# d2101-lofi-delay.net
KiCad netlist of a schematic drawn in EAGLE
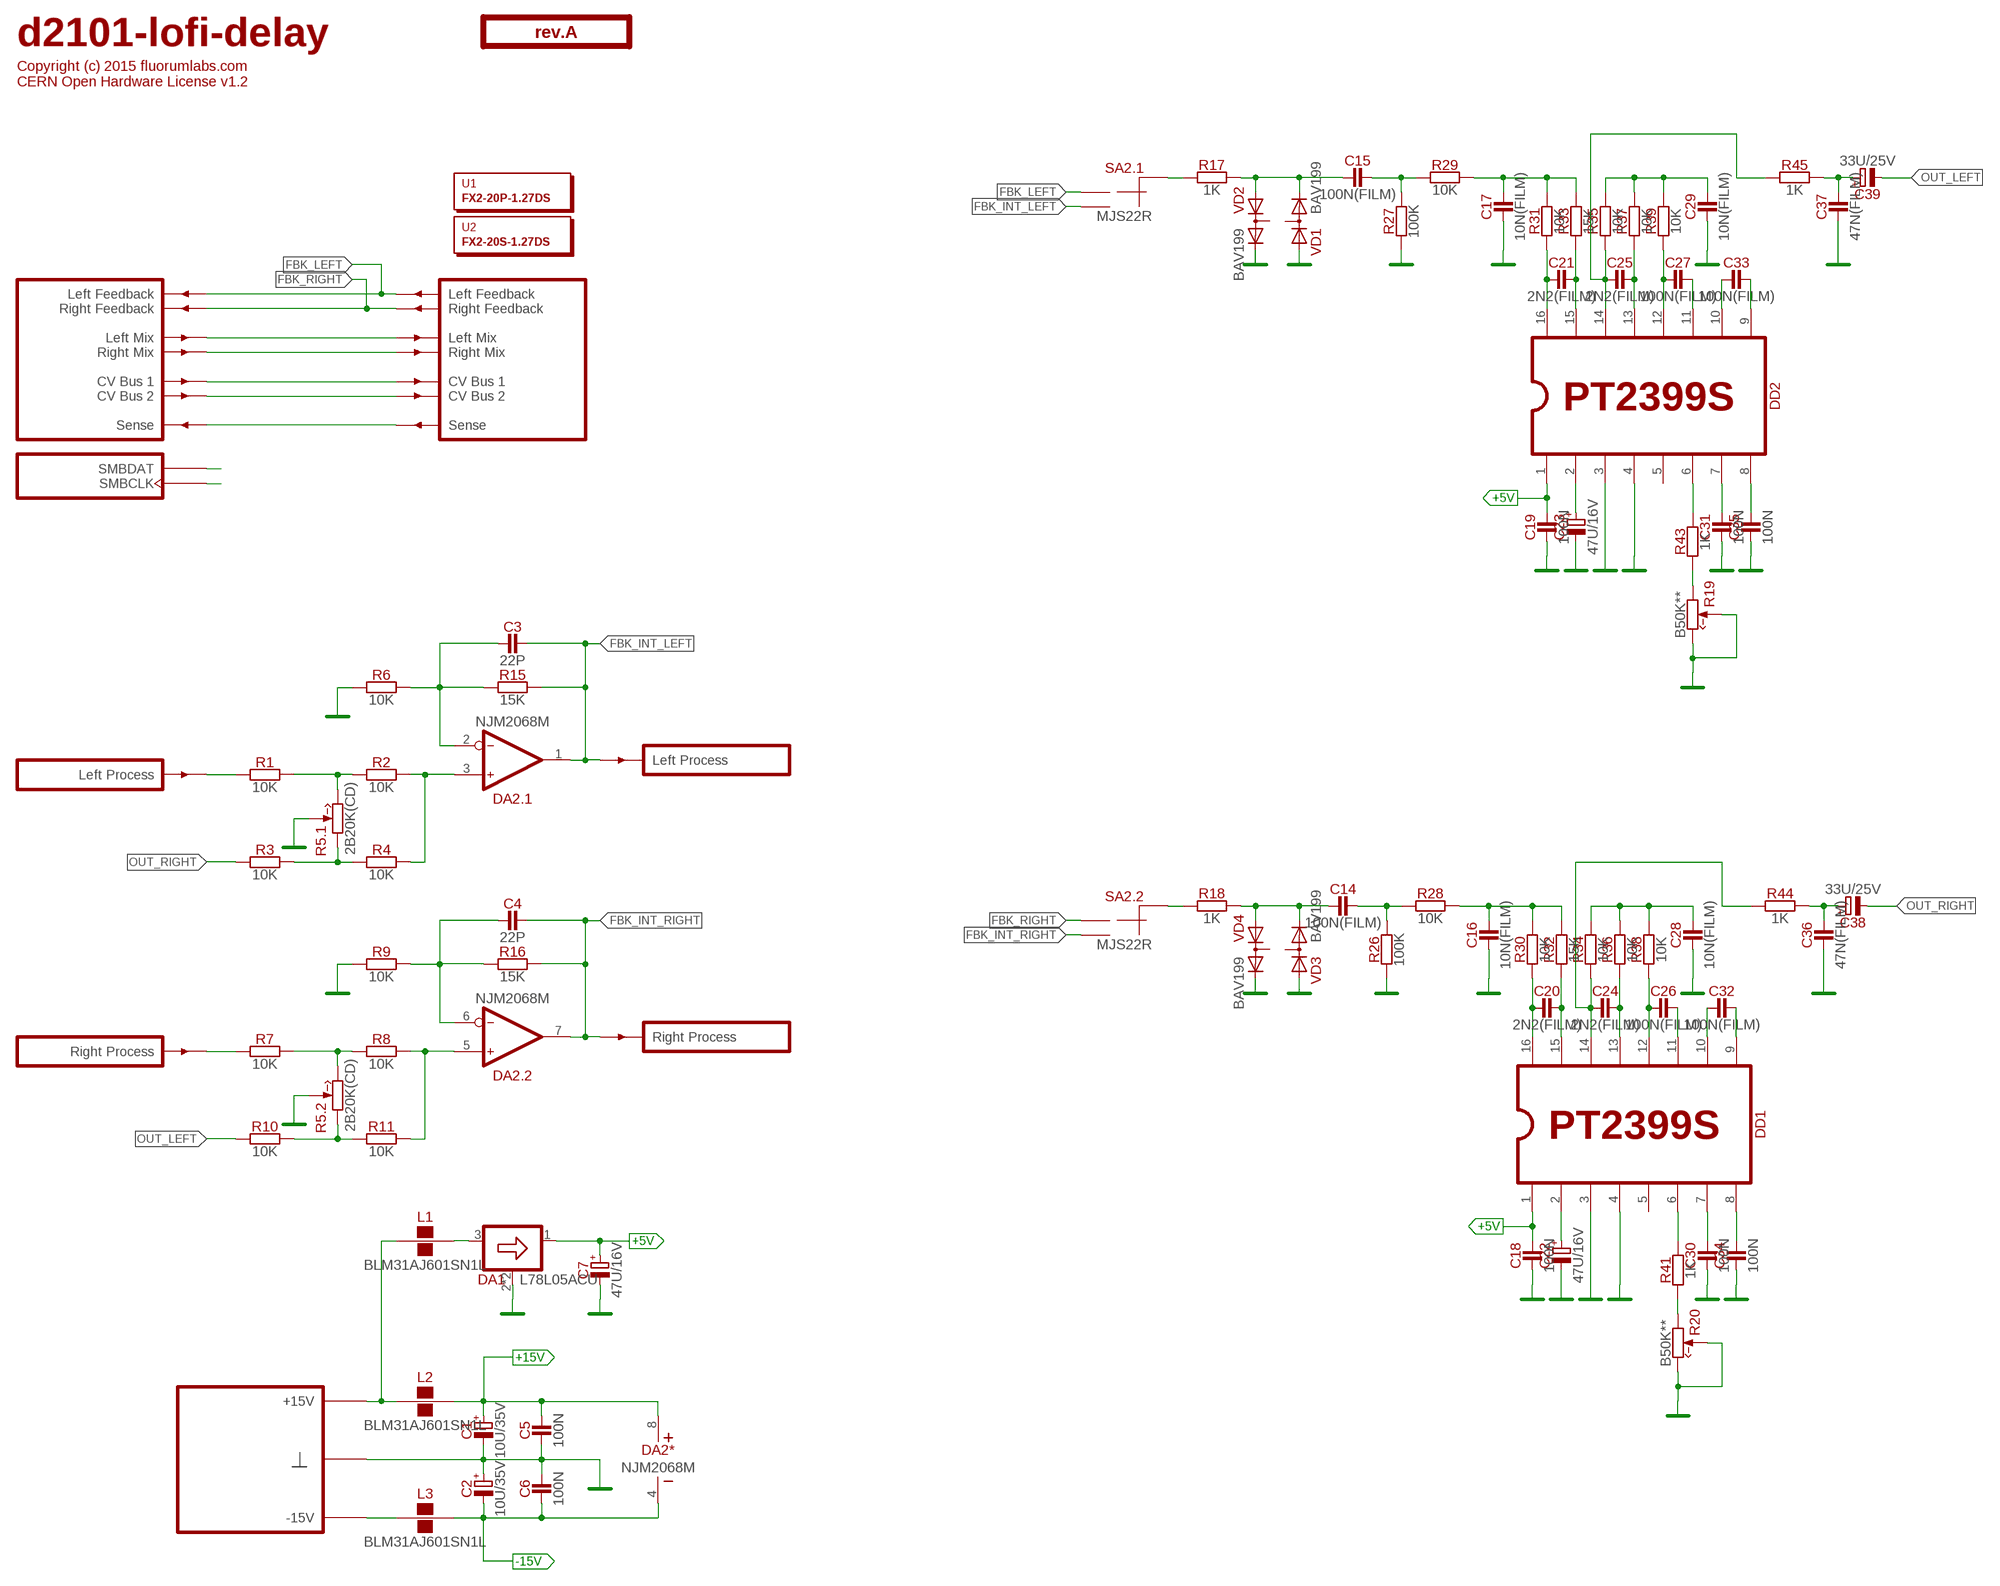
[diagram p0: schematic, sheet 1]

(export (version "E")
  (design (tool "Eeschema 10.0.6"))
  (components
    (comp (ref "C1")
      (value "10U/35V")
      (footprint "eagle-import:E2-5")
      (libsource (lib "eagle-import") (part "?10U/35V"))
    )
    (comp (ref "C2")
      (value "10U/35V")
      (footprint "eagle-import:E2-5")
      (libsource (lib "eagle-import") (part "?10U/35V"))
    )
    (comp (ref "C3")
      (value "22P")
      (footprint "eagle-import:C-0805")
      (libsource (lib "eagle-import") (part "?22P"))
    )
    (comp (ref "C4")
      (value "22P")
      (footprint "eagle-import:C-0805")
      (libsource (lib "eagle-import") (part "?22P"))
    )
    (comp (ref "C5")
      (value "100N")
      (footprint "eagle-import:C-0805")
      (libsource (lib "eagle-import") (part "?100N"))
    )
    (comp (ref "C6")
      (value "100N")
      (footprint "eagle-import:C-0805")
      (libsource (lib "eagle-import") (part "?100N"))
    )
    (comp (ref "C7")
      (value "47U/16V")
      (footprint "eagle-import:E2-5")
      (libsource (lib "eagle-import") (part "?47U/16V"))
    )
    (comp (ref "C14")
      (value "100N(FILM)")
      (footprint "eagle-import:C050-025X075")
      (libsource (lib "eagle-import") (part "?100N(FILM)"))
    )
    (comp (ref "C15")
      (value "100N(FILM)")
      (footprint "eagle-import:C050-025X075")
      (libsource (lib "eagle-import") (part "?100N(FILM)"))
    )
    (comp (ref "C16")
      (value "10N(FILM)")
      (footprint "eagle-import:C050-025X075")
      (libsource (lib "eagle-import") (part "?10N(FILM)"))
    )
    (comp (ref "C17")
      (value "10N(FILM)")
      (footprint "eagle-import:C050-025X075")
      (libsource (lib "eagle-import") (part "?10N(FILM)"))
    )
    (comp (ref "C18")
      (value "100N")
      (footprint "eagle-import:C-0805")
      (libsource (lib "eagle-import") (part "?100N"))
    )
    (comp (ref "C19")
      (value "100N")
      (footprint "eagle-import:C-0805")
      (libsource (lib "eagle-import") (part "?100N"))
    )
    (comp (ref "C20")
      (value "2N2(FILM)")
      (footprint "eagle-import:C050-025X075")
      (libsource (lib "eagle-import") (part "?2N2(FILM)"))
    )
    (comp (ref "C21")
      (value "2N2(FILM)")
      (footprint "eagle-import:C050-025X075")
      (libsource (lib "eagle-import") (part "?2N2(FILM)"))
    )
    (comp (ref "C22")
      (value "47U/16V")
      (footprint "eagle-import:E2-5")
      (libsource (lib "eagle-import") (part "?47U/16V"))
    )
    (comp (ref "C23")
      (value "47U/16V")
      (footprint "eagle-import:E2-5")
      (libsource (lib "eagle-import") (part "?47U/16V"))
    )
    (comp (ref "C24")
      (value "2N2(FILM)")
      (footprint "eagle-import:C050-025X075")
      (libsource (lib "eagle-import") (part "?2N2(FILM)"))
    )
    (comp (ref "C25")
      (value "2N2(FILM)")
      (footprint "eagle-import:C050-025X075")
      (libsource (lib "eagle-import") (part "?2N2(FILM)"))
    )
    (comp (ref "C26")
      (value "100N(FILM)")
      (footprint "eagle-import:C050-025X075")
      (libsource (lib "eagle-import") (part "?100N(FILM)"))
    )
    (comp (ref "C27")
      (value "100N(FILM)")
      (footprint "eagle-import:C050-025X075")
      (libsource (lib "eagle-import") (part "?100N(FILM)"))
    )
    (comp (ref "C28")
      (value "10N(FILM)")
      (footprint "eagle-import:C050-025X075")
      (libsource (lib "eagle-import") (part "?10N(FILM)"))
    )
    (comp (ref "C29")
      (value "10N(FILM)")
      (footprint "eagle-import:C050-025X075")
      (libsource (lib "eagle-import") (part "?10N(FILM)"))
    )
    (comp (ref "C30")
      (value "100N")
      (footprint "eagle-import:C-0805")
      (libsource (lib "eagle-import") (part "?100N"))
    )
    (comp (ref "C31")
      (value "100N")
      (footprint "eagle-import:C-0805")
      (libsource (lib "eagle-import") (part "?100N"))
    )
    (comp (ref "C32")
      (value "100N(FILM)")
      (footprint "eagle-import:C050-025X075")
      (libsource (lib "eagle-import") (part "?100N(FILM)"))
    )
    (comp (ref "C33")
      (value "100N(FILM)")
      (footprint "eagle-import:C050-025X075")
      (libsource (lib "eagle-import") (part "?100N(FILM)"))
    )
    (comp (ref "C34")
      (value "100N")
      (footprint "eagle-import:C-0805")
      (libsource (lib "eagle-import") (part "?100N"))
    )
    (comp (ref "C35")
      (value "100N")
      (footprint "eagle-import:C-0805")
      (libsource (lib "eagle-import") (part "?100N"))
    )
    (comp (ref "C36")
      (value "47N(FILM)")
      (footprint "eagle-import:C050-025X075")
      (libsource (lib "eagle-import") (part "?47N(FILM)"))
    )
    (comp (ref "C37")
      (value "47N(FILM)")
      (footprint "eagle-import:C050-025X075")
      (libsource (lib "eagle-import") (part "?47N(FILM)"))
    )
    (comp (ref "C38")
      (value "33U/25V")
      (footprint "eagle-import:E2,5-7")
      (libsource (lib "eagle-import") (part "?33U/25V"))
    )
    (comp (ref "C39")
      (value "33U/25V")
      (footprint "eagle-import:E2,5-7")
      (libsource (lib "eagle-import") (part "?33U/25V"))
    )
    (comp (ref "DA1")
      (value "L78L05ACU")
      (footprint "eagle-import:SOT89")
      (libsource (lib "eagle-import") (part "?L78L05ACU"))
    )
    (comp (ref "DA2")
      (value "NJM2068M")
      (footprint "eagle-import:SO-8")
      (libsource (lib "eagle-import") (part "NJM2068M"))
    )
    (comp (ref "DD1")
      (value "PT2399S")
      (footprint "eagle-import:SO-16")
      (libsource (lib "eagle-import") (part "PT2399S"))
    )
    (comp (ref "DD2")
      (value "PT2399S")
      (footprint "eagle-import:SO-16")
      (libsource (lib "eagle-import") (part "PT2399S"))
    )
    (comp (ref "L1")
      (value "BLM31AJ601SN1L")
      (footprint "eagle-import:1206")
      (libsource (lib "eagle-import") (part "BLM31AJ601SN1L"))
    )
    (comp (ref "L2")
      (value "BLM31AJ601SN1L")
      (footprint "eagle-import:1206")
      (libsource (lib "eagle-import") (part "BLM31AJ601SN1L"))
    )
    (comp (ref "L3")
      (value "BLM31AJ601SN1L")
      (footprint "eagle-import:1206")
      (libsource (lib "eagle-import") (part "BLM31AJ601SN1L"))
    )
    (comp (ref "O1")
      (value "TITLE")
      (footprint "eagle-import:EMPTY")
      (libsource (lib "eagle-import") (part "TITLE"))
    )
    (comp (ref "PCB1")
      (value "rev.A")
      (footprint "eagle-import:ST2-BOARD-50")
      (libsource (lib "eagle-import") (part "ST2-BOARD-50"))
    )
    (comp (ref "R1")
      (value "10K")
      (footprint "eagle-import:R-0805")
      (libsource (lib "eagle-import") (part "?10K"))
    )
    (comp (ref "R2")
      (value "10K")
      (footprint "eagle-import:R-0805")
      (libsource (lib "eagle-import") (part "?10K"))
    )
    (comp (ref "R3")
      (value "10K")
      (footprint "eagle-import:R-0805")
      (libsource (lib "eagle-import") (part "?10K"))
    )
    (comp (ref "R4")
      (value "10K")
      (footprint "eagle-import:R-0805")
      (libsource (lib "eagle-import") (part "?10K"))
    )
    (comp (ref "R5")
      (value "2B20K(CD)")
      (footprint "eagle-import:RV11-DUAL")
      (libsource (lib "eagle-import") (part "2?B20K(CD)"))
    )
    (comp (ref "R6")
      (value "10K")
      (footprint "eagle-import:R-0805")
      (libsource (lib "eagle-import") (part "?10K"))
    )
    (comp (ref "R7")
      (value "10K")
      (footprint "eagle-import:R-0805")
      (libsource (lib "eagle-import") (part "?10K"))
    )
    (comp (ref "R8")
      (value "10K")
      (footprint "eagle-import:R-0805")
      (libsource (lib "eagle-import") (part "?10K"))
    )
    (comp (ref "R9")
      (value "10K")
      (footprint "eagle-import:R-0805")
      (libsource (lib "eagle-import") (part "?10K"))
    )
    (comp (ref "R10")
      (value "10K")
      (footprint "eagle-import:R-0805")
      (libsource (lib "eagle-import") (part "?10K"))
    )
    (comp (ref "R11")
      (value "10K")
      (footprint "eagle-import:R-0805")
      (libsource (lib "eagle-import") (part "?10K"))
    )
    (comp (ref "R15")
      (value "15K")
      (footprint "eagle-import:R-0805")
      (libsource (lib "eagle-import") (part "?15K"))
    )
    (comp (ref "R16")
      (value "15K")
      (footprint "eagle-import:R-0805")
      (libsource (lib "eagle-import") (part "?15K"))
    )
    (comp (ref "R17")
      (value "1K")
      (footprint "eagle-import:R-0805")
      (libsource (lib "eagle-import") (part "?1K"))
    )
    (comp (ref "R18")
      (value "1K")
      (footprint "eagle-import:R-0805")
      (libsource (lib "eagle-import") (part "?1K"))
    )
    (comp (ref "R19")
      (value "B50K**")
      (footprint "eagle-import:RV11-SINGLE")
      (libsource (lib "eagle-import") (part "?B50K"))
    )
    (comp (ref "R20")
      (value "B50K**")
      (footprint "eagle-import:RV11-SINGLE")
      (libsource (lib "eagle-import") (part "?B50K"))
    )
    (comp (ref "R26")
      (value "100K")
      (footprint "eagle-import:R-0805")
      (libsource (lib "eagle-import") (part "?100K"))
    )
    (comp (ref "R27")
      (value "100K")
      (footprint "eagle-import:R-0805")
      (libsource (lib "eagle-import") (part "?100K"))
    )
    (comp (ref "R28")
      (value "10K")
      (footprint "eagle-import:R-0805")
      (libsource (lib "eagle-import") (part "?10K"))
    )
    (comp (ref "R29")
      (value "10K")
      (footprint "eagle-import:R-0805")
      (libsource (lib "eagle-import") (part "?10K"))
    )
    (comp (ref "R30")
      (value "10K")
      (footprint "eagle-import:R-0805")
      (libsource (lib "eagle-import") (part "?10K"))
    )
    (comp (ref "R31")
      (value "10K")
      (footprint "eagle-import:R-0805")
      (libsource (lib "eagle-import") (part "?10K"))
    )
    (comp (ref "R32")
      (value "15K")
      (footprint "eagle-import:R-0805")
      (libsource (lib "eagle-import") (part "?15K"))
    )
    (comp (ref "R33")
      (value "15K")
      (footprint "eagle-import:R-0805")
      (libsource (lib "eagle-import") (part "?15K"))
    )
    (comp (ref "R34")
      (value "10K")
      (footprint "eagle-import:R-0805")
      (libsource (lib "eagle-import") (part "?10K"))
    )
    (comp (ref "R35")
      (value "10K")
      (footprint "eagle-import:R-0805")
      (libsource (lib "eagle-import") (part "?10K"))
    )
    (comp (ref "R36")
      (value "10K")
      (footprint "eagle-import:R-0805")
      (libsource (lib "eagle-import") (part "?10K"))
    )
    (comp (ref "R37")
      (value "10K")
      (footprint "eagle-import:R-0805")
      (libsource (lib "eagle-import") (part "?10K"))
    )
    (comp (ref "R38")
      (value "10K")
      (footprint "eagle-import:R-0805")
      (libsource (lib "eagle-import") (part "?10K"))
    )
    (comp (ref "R39")
      (value "10K")
      (footprint "eagle-import:R-0805")
      (libsource (lib "eagle-import") (part "?10K"))
    )
    (comp (ref "R41")
      (value "1K")
      (footprint "eagle-import:R-0805")
      (libsource (lib "eagle-import") (part "?1K"))
    )
    (comp (ref "R43")
      (value "1K")
      (footprint "eagle-import:R-0805")
      (libsource (lib "eagle-import") (part "?1K"))
    )
    (comp (ref "R44")
      (value "1K")
      (footprint "eagle-import:R-0805")
      (libsource (lib "eagle-import") (part "?1K"))
    )
    (comp (ref "R45")
      (value "1K")
      (footprint "eagle-import:R-0805")
      (libsource (lib "eagle-import") (part "?1K"))
    )
    (comp (ref "SA2")
      (value "MJS22R")
      (footprint "eagle-import:APEM-MJS22R")
      (libsource (lib "eagle-import") (part "MJS22R"))
    )
    (comp (ref "U1")
      (value "FX2-20P-1.27DS")
      (footprint "eagle-import:EMPTY")
      (libsource (lib "eagle-import") (part "?FX2-20P-1.27DS"))
    )
    (comp (ref "U2")
      (value "FX2-20S-1.27DS")
      (footprint "eagle-import:EMPTY")
      (libsource (lib "eagle-import") (part "?FX2-20S-1.27DS"))
    )
    (comp (ref "VD1")
      (value "BAV199")
      (footprint "eagle-import:SOT23")
      (libsource (lib "eagle-import") (part "BAV199"))
    )
    (comp (ref "VD2")
      (value "BAV199")
      (footprint "eagle-import:SOT23")
      (libsource (lib "eagle-import") (part "BAV199"))
    )
    (comp (ref "VD3")
      (value "BAV199")
      (footprint "eagle-import:SOT23")
      (libsource (lib "eagle-import") (part "BAV199"))
    )
    (comp (ref "VD4")
      (value "BAV199")
      (footprint "eagle-import:SOT23")
      (libsource (lib "eagle-import") (part "BAV199"))
    )
  )
  (nets
    (net (code "1") (name "+5V") (class "Default")
      (node (ref "C18") (pin "2") (pinfunction "2_2") (pintype "passive"))
      (node (ref "C19") (pin "2") (pinfunction "2_2") (pintype "passive"))
      (node (ref "C7") (pin "+") (pinfunction "+_+") (pintype "passive"))
      (node (ref "DA1") (pin "1") (pinfunction "OUT_1") (pintype "power_in"))
      (node (ref "DD1") (pin "1") (pinfunction "1_1") (pintype "bidirectional"))
      (node (ref "DD2") (pin "1") (pinfunction "1_1") (pintype "bidirectional"))
    )
    (net (code "2") (name "+15V") (class "Default")
      (node (ref "C1") (pin "+") (pinfunction "+_+") (pintype "passive"))
      (node (ref "C5") (pin "2") (pinfunction "2_2") (pintype "passive"))
      (node (ref "DA2") (pin "8") (pinfunction "V+_8") (pintype "power_in"))
      (node (ref "L2") (pin "2") (pinfunction "2_2") (pintype "passive"))
    )
    (net (code "3") (name "-15V") (class "Default")
      (node (ref "C2") (pin "-") (pinfunction "-_-") (pintype "passive"))
      (node (ref "C6") (pin "1") (pinfunction "1_1") (pintype "passive"))
      (node (ref "DA2") (pin "4") (pinfunction "V-_4") (pintype "power_in"))
      (node (ref "L3") (pin "2") (pinfunction "2_2") (pintype "passive"))
    )
    (net (code "4") (name "FBK_INT_LEFT") (class "Default")
      (node (ref "C3") (pin "2") (pinfunction "2_2") (pintype "passive"))
      (node (ref "DA2") (pin "1") (pinfunction "OUT_1") (pintype "output"))
      (node (ref "PCB1") (pin "BOUTL'") (pinfunction "OUTL_BOUTL'") (pintype "bidirectional"))
      (node (ref "R15") (pin "2") (pinfunction "2_2") (pintype "passive"))
      (node (ref "SA2") (pin "NO1") (pinfunction "2_NO1") (pintype "passive"))
    )
    (net (code "5") (name "FBK_INT_RIGHT") (class "Default")
      (node (ref "C4") (pin "2") (pinfunction "2_2") (pintype "passive"))
      (node (ref "DA2") (pin "7") (pinfunction "OUT_7") (pintype "output"))
      (node (ref "PCB1") (pin "BOUTR'") (pinfunction "OUTR_BOUTR'") (pintype "bidirectional"))
      (node (ref "R16") (pin "2") (pinfunction "2_2") (pintype "passive"))
      (node (ref "SA2") (pin "NO2") (pinfunction "2_NO2") (pintype "passive"))
    )
    (net (code "6") (name "FBK_LEFT") (class "Default")
      (node (ref "PCB1") (pin "ALFBK") (pinfunction "LFBK_ALFBK") (pintype "bidirectional"))
      (node (ref "PCB1") (pin "ALFBK'") (pinfunction "LFBK'_ALFBK'") (pintype "bidirectional"))
      (node (ref "SA2") (pin "NC1") (pinfunction "1_NC1") (pintype "passive"))
    )
    (net (code "7") (name "FBK_RIGHT") (class "Default")
      (node (ref "PCB1") (pin "ARFBK") (pinfunction "RFBK_ARFBK") (pintype "bidirectional"))
      (node (ref "PCB1") (pin "ARFBK'") (pinfunction "RFBK'_ARFBK'") (pintype "bidirectional"))
      (node (ref "SA2") (pin "NC2") (pinfunction "1_NC2") (pintype "passive"))
    )
    (net (code "8") (name "GND") (class "Default")
      (node (ref "C1") (pin "-") (pinfunction "-_-") (pintype "passive"))
      (node (ref "C16") (pin "1") (pinfunction "1_1") (pintype "passive"))
      (node (ref "C17") (pin "1") (pinfunction "1_1") (pintype "passive"))
      (node (ref "C18") (pin "1") (pinfunction "1_1") (pintype "passive"))
      (node (ref "C19") (pin "1") (pinfunction "1_1") (pintype "passive"))
      (node (ref "C2") (pin "+") (pinfunction "+_+") (pintype "passive"))
      (node (ref "C22") (pin "-") (pinfunction "-_-") (pintype "passive"))
      (node (ref "C23") (pin "-") (pinfunction "-_-") (pintype "passive"))
      (node (ref "C28") (pin "1") (pinfunction "1_1") (pintype "passive"))
      (node (ref "C29") (pin "1") (pinfunction "1_1") (pintype "passive"))
      (node (ref "C30") (pin "1") (pinfunction "1_1") (pintype "passive"))
      (node (ref "C31") (pin "1") (pinfunction "1_1") (pintype "passive"))
      (node (ref "C34") (pin "1") (pinfunction "1_1") (pintype "passive"))
      (node (ref "C35") (pin "1") (pinfunction "1_1") (pintype "passive"))
      (node (ref "C36") (pin "1") (pinfunction "1_1") (pintype "passive"))
      (node (ref "C37") (pin "1") (pinfunction "1_1") (pintype "passive"))
      (node (ref "C5") (pin "1") (pinfunction "1_1") (pintype "passive"))
      (node (ref "C6") (pin "2") (pinfunction "2_2") (pintype "passive"))
      (node (ref "C7") (pin "-") (pinfunction "-_-") (pintype "passive"))
      (node (ref "DA1") (pin "2") (pinfunction "GND_2") (pintype "power_in"))
      (node (ref "DA1") (pin "2@1") (pinfunction "GND_2@1") (pintype "power_in"))
      (node (ref "DD1") (pin "3") (pinfunction "3_3") (pintype "bidirectional"))
      (node (ref "DD1") (pin "4") (pinfunction "4_4") (pintype "bidirectional"))
      (node (ref "DD2") (pin "3") (pinfunction "3_3") (pintype "bidirectional"))
      (node (ref "DD2") (pin "4") (pinfunction "4_4") (pintype "bidirectional"))
      (node (ref "PCB1") (pin "B4") (pinfunction "GND_B4") (pintype "bidirectional"))
      (node (ref "PCB1") (pin "B4'") (pinfunction "GND_B4'") (pintype "bidirectional"))
      (node (ref "PCB1") (pin "B5") (pinfunction "GND_B5") (pintype "bidirectional"))
      (node (ref "PCB1") (pin "B5'") (pinfunction "GND_B5'") (pintype "bidirectional"))
      (node (ref "PCB1") (pin "B6") (pinfunction "GND_B6") (pintype "bidirectional"))
      (node (ref "PCB1") (pin "B6'") (pinfunction "GND_B6'") (pintype "bidirectional"))
      (node (ref "PCB1") (pin "B7") (pinfunction "GND_B7") (pintype "bidirectional"))
      (node (ref "PCB1") (pin "B7'") (pinfunction "GND_B7'") (pintype "bidirectional"))
      (node (ref "PCB1") (pin "B8") (pinfunction "GND_B8") (pintype "bidirectional"))
      (node (ref "PCB1") (pin "B8'") (pinfunction "GND_B8'") (pintype "bidirectional"))
      (node (ref "R19") (pin "2") (pinfunction "W_2") (pintype "passive"))
      (node (ref "R19") (pin "3") (pinfunction "CW_3") (pintype "passive"))
      (node (ref "R20") (pin "2") (pinfunction "W_2") (pintype "passive"))
      (node (ref "R20") (pin "3") (pinfunction "CW_3") (pintype "passive"))
      (node (ref "R26") (pin "1") (pinfunction "1_1") (pintype "passive"))
      (node (ref "R27") (pin "1") (pinfunction "1_1") (pintype "passive"))
      (node (ref "R5") (pin "2") (pinfunction "W_2") (pintype "passive"))
      (node (ref "R5") (pin "2'") (pinfunction "W_2'") (pintype "passive"))
      (node (ref "R6") (pin "1") (pinfunction "1_1") (pintype "passive"))
      (node (ref "R9") (pin "1") (pinfunction "1_1") (pintype "passive"))
      (node (ref "VD1") (pin "1") (pinfunction "A_1") (pintype "passive"))
      (node (ref "VD2") (pin "2") (pinfunction "C_2") (pintype "passive"))
      (node (ref "VD3") (pin "1") (pinfunction "A_1") (pintype "passive"))
      (node (ref "VD4") (pin "2") (pinfunction "C_2") (pintype "passive"))
    )
    (net (code "9") (name "Net-(C14-Pad2)") (class "Default")
      (node (ref "C14") (pin "2") (pinfunction "2_2") (pintype "passive"))
      (node (ref "R26") (pin "2") (pinfunction "2_2") (pintype "passive"))
      (node (ref "R28") (pin "1") (pinfunction "1_1") (pintype "passive"))
    )
    (net (code "10") (name "Net-(C15-Pad2)") (class "Default")
      (node (ref "C15") (pin "2") (pinfunction "2_2") (pintype "passive"))
      (node (ref "R27") (pin "2") (pinfunction "2_2") (pintype "passive"))
      (node (ref "R29") (pin "1") (pinfunction "1_1") (pintype "passive"))
    )
    (net (code "11") (name "Net-(C16-Pad2)") (class "Default")
      (node (ref "C16") (pin "2") (pinfunction "2_2") (pintype "passive"))
      (node (ref "R28") (pin "2") (pinfunction "2_2") (pintype "passive"))
      (node (ref "R30") (pin "2") (pinfunction "2_2") (pintype "passive"))
      (node (ref "R32") (pin "2") (pinfunction "2_2") (pintype "passive"))
    )
    (net (code "12") (name "Net-(C17-Pad2)") (class "Default")
      (node (ref "C17") (pin "2") (pinfunction "2_2") (pintype "passive"))
      (node (ref "R29") (pin "2") (pinfunction "2_2") (pintype "passive"))
      (node (ref "R31") (pin "2") (pinfunction "2_2") (pintype "passive"))
      (node (ref "R33") (pin "2") (pinfunction "2_2") (pintype "passive"))
    )
    (net (code "13") (name "Net-(C20-Pad1)") (class "Default")
      (node (ref "C20") (pin "1") (pinfunction "1_1") (pintype "passive"))
      (node (ref "DD1") (pin "16") (pinfunction "16_16") (pintype "bidirectional"))
      (node (ref "R30") (pin "1") (pinfunction "1_1") (pintype "passive"))
    )
    (net (code "14") (name "Net-(C20-Pad2)") (class "Default")
      (node (ref "C20") (pin "2") (pinfunction "2_2") (pintype "passive"))
      (node (ref "DD1") (pin "15") (pinfunction "15_15") (pintype "bidirectional"))
      (node (ref "R32") (pin "1") (pinfunction "1_1") (pintype "passive"))
    )
    (net (code "15") (name "Net-(C21-Pad1)") (class "Default")
      (node (ref "C21") (pin "1") (pinfunction "1_1") (pintype "passive"))
      (node (ref "DD2") (pin "16") (pinfunction "16_16") (pintype "bidirectional"))
      (node (ref "R31") (pin "1") (pinfunction "1_1") (pintype "passive"))
    )
    (net (code "16") (name "Net-(C21-Pad2)") (class "Default")
      (node (ref "C21") (pin "2") (pinfunction "2_2") (pintype "passive"))
      (node (ref "DD2") (pin "15") (pinfunction "15_15") (pintype "bidirectional"))
      (node (ref "R33") (pin "1") (pinfunction "1_1") (pintype "passive"))
    )
    (net (code "17") (name "Net-(C22-Pad+)") (class "Default")
      (node (ref "C22") (pin "+") (pinfunction "+_+") (pintype "passive"))
      (node (ref "DD1") (pin "2") (pinfunction "2_2") (pintype "bidirectional"))
    )
    (net (code "18") (name "Net-(C23-Pad+)") (class "Default")
      (node (ref "C23") (pin "+") (pinfunction "+_+") (pintype "passive"))
      (node (ref "DD2") (pin "2") (pinfunction "2_2") (pintype "bidirectional"))
    )
    (net (code "19") (name "Net-(C24-Pad1)") (class "Default")
      (node (ref "C24") (pin "1") (pinfunction "1_1") (pintype "passive"))
      (node (ref "DD1") (pin "14") (pinfunction "14_14") (pintype "bidirectional"))
      (node (ref "R34") (pin "1") (pinfunction "1_1") (pintype "passive"))
      (node (ref "R44") (pin "1") (pinfunction "1_1") (pintype "passive"))
    )
    (net (code "20") (name "Net-(C24-Pad2)") (class "Default")
      (node (ref "C24") (pin "2") (pinfunction "2_2") (pintype "passive"))
      (node (ref "DD1") (pin "13") (pinfunction "13_13") (pintype "bidirectional"))
      (node (ref "R36") (pin "1") (pinfunction "1_1") (pintype "passive"))
    )
    (net (code "21") (name "Net-(C25-Pad1)") (class "Default")
      (node (ref "C25") (pin "1") (pinfunction "1_1") (pintype "passive"))
      (node (ref "DD2") (pin "14") (pinfunction "14_14") (pintype "bidirectional"))
      (node (ref "R35") (pin "1") (pinfunction "1_1") (pintype "passive"))
      (node (ref "R45") (pin "1") (pinfunction "1_1") (pintype "passive"))
    )
    (net (code "22") (name "Net-(C25-Pad2)") (class "Default")
      (node (ref "C25") (pin "2") (pinfunction "2_2") (pintype "passive"))
      (node (ref "DD2") (pin "13") (pinfunction "13_13") (pintype "bidirectional"))
      (node (ref "R37") (pin "1") (pinfunction "1_1") (pintype "passive"))
    )
    (net (code "23") (name "Net-(C26-Pad1)") (class "Default")
      (node (ref "C26") (pin "1") (pinfunction "1_1") (pintype "passive"))
      (node (ref "DD1") (pin "12") (pinfunction "12_12") (pintype "bidirectional"))
      (node (ref "R38") (pin "1") (pinfunction "1_1") (pintype "passive"))
    )
    (net (code "24") (name "Net-(C26-Pad2)") (class "Default")
      (node (ref "C26") (pin "2") (pinfunction "2_2") (pintype "passive"))
      (node (ref "DD1") (pin "11") (pinfunction "11_11") (pintype "bidirectional"))
    )
    (net (code "25") (name "Net-(C27-Pad1)") (class "Default")
      (node (ref "C27") (pin "1") (pinfunction "1_1") (pintype "passive"))
      (node (ref "DD2") (pin "12") (pinfunction "12_12") (pintype "bidirectional"))
      (node (ref "R39") (pin "1") (pinfunction "1_1") (pintype "passive"))
    )
    (net (code "26") (name "Net-(C27-Pad2)") (class "Default")
      (node (ref "C27") (pin "2") (pinfunction "2_2") (pintype "passive"))
      (node (ref "DD2") (pin "11") (pinfunction "11_11") (pintype "bidirectional"))
    )
    (net (code "27") (name "Net-(C28-Pad2)") (class "Default")
      (node (ref "C28") (pin "2") (pinfunction "2_2") (pintype "passive"))
      (node (ref "R34") (pin "2") (pinfunction "2_2") (pintype "passive"))
      (node (ref "R36") (pin "2") (pinfunction "2_2") (pintype "passive"))
      (node (ref "R38") (pin "2") (pinfunction "2_2") (pintype "passive"))
    )
    (net (code "28") (name "Net-(C29-Pad2)") (class "Default")
      (node (ref "C29") (pin "2") (pinfunction "2_2") (pintype "passive"))
      (node (ref "R35") (pin "2") (pinfunction "2_2") (pintype "passive"))
      (node (ref "R37") (pin "2") (pinfunction "2_2") (pintype "passive"))
      (node (ref "R39") (pin "2") (pinfunction "2_2") (pintype "passive"))
    )
    (net (code "29") (name "Net-(C30-Pad2)") (class "Default")
      (node (ref "C30") (pin "2") (pinfunction "2_2") (pintype "passive"))
      (node (ref "DD1") (pin "7") (pinfunction "7_7") (pintype "bidirectional"))
    )
    (net (code "30") (name "Net-(C31-Pad2)") (class "Default")
      (node (ref "C31") (pin "2") (pinfunction "2_2") (pintype "passive"))
      (node (ref "DD2") (pin "7") (pinfunction "7_7") (pintype "bidirectional"))
    )
    (net (code "31") (name "Net-(C32-Pad1)") (class "Default")
      (node (ref "C32") (pin "1") (pinfunction "1_1") (pintype "passive"))
      (node (ref "DD1") (pin "10") (pinfunction "10_10") (pintype "bidirectional"))
    )
    (net (code "32") (name "Net-(C32-Pad2)") (class "Default")
      (node (ref "C32") (pin "2") (pinfunction "2_2") (pintype "passive"))
      (node (ref "DD1") (pin "9") (pinfunction "9_9") (pintype "bidirectional"))
    )
    (net (code "33") (name "Net-(C33-Pad1)") (class "Default")
      (node (ref "C33") (pin "1") (pinfunction "1_1") (pintype "passive"))
      (node (ref "DD2") (pin "10") (pinfunction "10_10") (pintype "bidirectional"))
    )
    (net (code "34") (name "Net-(C33-Pad2)") (class "Default")
      (node (ref "C33") (pin "2") (pinfunction "2_2") (pintype "passive"))
      (node (ref "DD2") (pin "9") (pinfunction "9_9") (pintype "bidirectional"))
    )
    (net (code "35") (name "Net-(C34-Pad2)") (class "Default")
      (node (ref "C34") (pin "2") (pinfunction "2_2") (pintype "passive"))
      (node (ref "DD1") (pin "8") (pinfunction "8_8") (pintype "bidirectional"))
    )
    (net (code "36") (name "Net-(C35-Pad2)") (class "Default")
      (node (ref "C35") (pin "2") (pinfunction "2_2") (pintype "passive"))
      (node (ref "DD2") (pin "8") (pinfunction "8_8") (pintype "bidirectional"))
    )
    (net (code "37") (name "Net-(C36-Pad2)") (class "Default")
      (node (ref "C36") (pin "2") (pinfunction "2_2") (pintype "passive"))
      (node (ref "C38") (pin "+") (pinfunction "+_+") (pintype "passive"))
      (node (ref "R44") (pin "2") (pinfunction "2_2") (pintype "passive"))
    )
    (net (code "38") (name "Net-(C37-Pad2)") (class "Default")
      (node (ref "C37") (pin "2") (pinfunction "2_2") (pintype "passive"))
      (node (ref "C39") (pin "+") (pinfunction "+_+") (pintype "passive"))
      (node (ref "R45") (pin "2") (pinfunction "2_2") (pintype "passive"))
    )
    (net (code "39") (name "Net-(DA1-IN)") (class "Default")
      (node (ref "DA1") (pin "3") (pinfunction "IN_3") (pintype "power_in"))
      (node (ref "L1") (pin "2") (pinfunction "2_2") (pintype "passive"))
    )
    (net (code "40") (name "Net-(DA2B-IN+)") (class "Default")
      (node (ref "DA2") (pin "3") (pinfunction "IN+_3") (pintype "input"))
      (node (ref "R2") (pin "2") (pinfunction "2_2") (pintype "passive"))
      (node (ref "R4") (pin "2") (pinfunction "2_2") (pintype "passive"))
    )
    (net (code "41") (name "Net-(DA2B-IN-)") (class "Default")
      (node (ref "C3") (pin "1") (pinfunction "1_1") (pintype "passive"))
      (node (ref "DA2") (pin "2") (pinfunction "IN-_2") (pintype "input"))
      (node (ref "R15") (pin "1") (pinfunction "1_1") (pintype "passive"))
      (node (ref "R6") (pin "2") (pinfunction "2_2") (pintype "passive"))
    )
    (net (code "42") (name "Net-(DA2C-IN+)") (class "Default")
      (node (ref "DA2") (pin "5") (pinfunction "IN+_5") (pintype "input"))
      (node (ref "R11") (pin "2") (pinfunction "2_2") (pintype "passive"))
      (node (ref "R8") (pin "2") (pinfunction "2_2") (pintype "passive"))
    )
    (net (code "43") (name "Net-(DA2C-IN-)") (class "Default")
      (node (ref "C4") (pin "1") (pinfunction "1_1") (pintype "passive"))
      (node (ref "DA2") (pin "6") (pinfunction "IN-_6") (pintype "input"))
      (node (ref "R16") (pin "1") (pinfunction "1_1") (pintype "passive"))
      (node (ref "R9") (pin "2") (pinfunction "2_2") (pintype "passive"))
    )
    (net (code "44") (name "Net-(DD1-Pad6)") (class "Default")
      (node (ref "DD1") (pin "6") (pinfunction "6_6") (pintype "bidirectional"))
      (node (ref "R41") (pin "2") (pinfunction "2_2") (pintype "passive"))
    )
    (net (code "45") (name "Net-(DD2-Pad6)") (class "Default")
      (node (ref "DD2") (pin "6") (pinfunction "6_6") (pintype "bidirectional"))
      (node (ref "R43") (pin "2") (pinfunction "2_2") (pintype "passive"))
    )
    (net (code "46") (name "Net-(L1-Pad1)") (class "Default")
      (node (ref "L1") (pin "1") (pinfunction "1_1") (pintype "passive"))
      (node (ref "L2") (pin "1") (pinfunction "1_1") (pintype "passive"))
      (node (ref "PCB1") (pin "A+15") (pinfunction "P+15V_A+15") (pintype "bidirectional"))
      (node (ref "PCB1") (pin "A+15'") (pinfunction "P+15V_A+15'") (pintype "bidirectional"))
      (node (ref "PCB1") (pin "B+15") (pinfunction "P+15V_B+15") (pintype "bidirectional"))
      (node (ref "PCB1") (pin "B+15'") (pinfunction "P+15V_B+15'") (pintype "bidirectional"))
    )
    (net (code "47") (name "Net-(L3-Pad1)") (class "Default")
      (node (ref "L3") (pin "1") (pinfunction "1_1") (pintype "passive"))
      (node (ref "PCB1") (pin "A-15") (pinfunction "P-15V_A-15") (pintype "bidirectional"))
      (node (ref "PCB1") (pin "A-15'") (pinfunction "P-15V_A-15'") (pintype "bidirectional"))
      (node (ref "PCB1") (pin "B-15") (pinfunction "P-15V_B-15") (pintype "bidirectional"))
      (node (ref "PCB1") (pin "B-15'") (pinfunction "P-15V_B-15'") (pintype "bidirectional"))
    )
    (net (code "48") (name "Net-(PCB1B-INL)") (class "Default")
      (node (ref "PCB1") (pin "BINL") (pinfunction "INL_BINL") (pintype "bidirectional"))
      (node (ref "R1") (pin "1") (pinfunction "1_1") (pintype "passive"))
    )
    (net (code "49") (name "Net-(PCB1C-INR)") (class "Default")
      (node (ref "PCB1") (pin "BINR") (pinfunction "INR_BINR") (pintype "bidirectional"))
      (node (ref "R7") (pin "1") (pinfunction "1_1") (pintype "passive"))
    )
    (net (code "50") (name "Net-(PCB1F-CV1)") (class "Default")
      (node (ref "PCB1") (pin "ACV1") (pinfunction "CV1_ACV1") (pintype "bidirectional"))
      (node (ref "PCB1") (pin "ACV1'") (pinfunction "CV1'_ACV1'") (pintype "bidirectional"))
    )
    (net (code "51") (name "Net-(PCB1F-CV2)") (class "Default")
      (node (ref "PCB1") (pin "ACV2") (pinfunction "CV2_ACV2") (pintype "bidirectional"))
      (node (ref "PCB1") (pin "ACV2'") (pinfunction "CV2'_ACV2'") (pintype "bidirectional"))
    )
    (net (code "52") (name "Net-(PCB1F-LMIX)") (class "Default")
      (node (ref "PCB1") (pin "ALMIX") (pinfunction "LMIX_ALMIX") (pintype "bidirectional"))
      (node (ref "PCB1") (pin "ALMIX'") (pinfunction "LMIX'_ALMIX'") (pintype "bidirectional"))
    )
    (net (code "53") (name "Net-(PCB1F-RMIX)") (class "Default")
      (node (ref "PCB1") (pin "ARMIX") (pinfunction "RMIX_ARMIX") (pintype "bidirectional"))
      (node (ref "PCB1") (pin "ARMIX'") (pinfunction "RMIX'_ARMIX'") (pintype "bidirectional"))
    )
    (net (code "54") (name "Net-(PCB1F-SENSE)") (class "Default")
      (node (ref "PCB1") (pin "BSENSE") (pinfunction "SENSE_BSENSE") (pintype "bidirectional"))
      (node (ref "PCB1") (pin "BSENSE'") (pinfunction "SENSE'_BSENSE'") (pintype "bidirectional"))
    )
    (net (code "55") (name "Net-(PCB1H-SMBCLK-PadASMBCLK')") (class "Default")
      (node (ref "PCB1") (pin "ASMBCLK") (pinfunction "SMBCLK_ASMBCLK") (pintype "bidirectional"))
      (node (ref "PCB1") (pin "ASMBCLK'") (pinfunction "SMBCLK_ASMBCLK'") (pintype "bidirectional"))
    )
    (net (code "56") (name "Net-(PCB1H-SMBDAT-PadASMBDAT')") (class "Default")
      (node (ref "PCB1") (pin "ASMBDAT") (pinfunction "SMBDAT_ASMBDAT") (pintype "bidirectional"))
      (node (ref "PCB1") (pin "ASMBDAT'") (pinfunction "SMBDAT_ASMBDAT'") (pintype "bidirectional"))
    )
    (net (code "57") (name "Net-(R5A-CCW)") (class "Default")
      (node (ref "R3") (pin "2") (pinfunction "2_2") (pintype "passive"))
      (node (ref "R4") (pin "1") (pinfunction "1_1") (pintype "passive"))
      (node (ref "R5") (pin "1") (pinfunction "CCW_1") (pintype "passive"))
    )
    (net (code "58") (name "Net-(R5A-CW)") (class "Default")
      (node (ref "R1") (pin "2") (pinfunction "2_2") (pintype "passive"))
      (node (ref "R2") (pin "1") (pinfunction "1_1") (pintype "passive"))
      (node (ref "R5") (pin "3") (pinfunction "CW_3") (pintype "passive"))
    )
    (net (code "59") (name "Net-(R5B-CCW)") (class "Default")
      (node (ref "R10") (pin "2") (pinfunction "2_2") (pintype "passive"))
      (node (ref "R11") (pin "1") (pinfunction "1_1") (pintype "passive"))
      (node (ref "R5") (pin "1'") (pinfunction "CCW_1'") (pintype "passive"))
    )
    (net (code "60") (name "Net-(R5B-CW)") (class "Default")
      (node (ref "R5") (pin "3'") (pinfunction "CW_3'") (pintype "passive"))
      (node (ref "R7") (pin "2") (pinfunction "2_2") (pintype "passive"))
      (node (ref "R8") (pin "1") (pinfunction "1_1") (pintype "passive"))
    )
    (net (code "61") (name "Net-(R19-CCW)") (class "Default")
      (node (ref "R19") (pin "1") (pinfunction "CCW_1") (pintype "passive"))
      (node (ref "R43") (pin "1") (pinfunction "1_1") (pintype "passive"))
    )
    (net (code "62") (name "Net-(R20-CCW)") (class "Default")
      (node (ref "R20") (pin "1") (pinfunction "CCW_1") (pintype "passive"))
      (node (ref "R41") (pin "1") (pinfunction "1_1") (pintype "passive"))
    )
    (net (code "63") (name "Net-(SA2A-CM)") (class "Default")
      (node (ref "R17") (pin "1") (pinfunction "1_1") (pintype "passive"))
      (node (ref "SA2") (pin "C1") (pinfunction "CM_C1") (pintype "passive"))
    )
    (net (code "64") (name "Net-(SA2B-CM)") (class "Default")
      (node (ref "R18") (pin "1") (pinfunction "1_1") (pintype "passive"))
      (node (ref "SA2") (pin "C2") (pinfunction "CM_C2") (pintype "passive"))
    )
    (net (code "65") (name "Net-(VD1-C)") (class "Default")
      (node (ref "C15") (pin "1") (pinfunction "1_1") (pintype "passive"))
      (node (ref "R17") (pin "2") (pinfunction "2_2") (pintype "passive"))
      (node (ref "VD1") (pin "2") (pinfunction "C_2") (pintype "passive"))
      (node (ref "VD2") (pin "1") (pinfunction "A_1") (pintype "passive"))
    )
    (net (code "66") (name "Net-(VD3-C)") (class "Default")
      (node (ref "C14") (pin "1") (pinfunction "1_1") (pintype "passive"))
      (node (ref "R18") (pin "2") (pinfunction "2_2") (pintype "passive"))
      (node (ref "VD3") (pin "2") (pinfunction "C_2") (pintype "passive"))
      (node (ref "VD4") (pin "1") (pinfunction "A_1") (pintype "passive"))
    )
    (net (code "67") (name "OUT_LEFT") (class "Default")
      (node (ref "C39") (pin "-") (pinfunction "-_-") (pintype "passive"))
      (node (ref "R10") (pin "1") (pinfunction "1_1") (pintype "passive"))
    )
    (net (code "68") (name "OUT_RIGHT") (class "Default")
      (node (ref "C38") (pin "-") (pinfunction "-_-") (pintype "passive"))
      (node (ref "R3") (pin "1") (pinfunction "1_1") (pintype "passive"))
    )
    (net (code "69") (name "unconnected-(DD1-Pad5)") (class "Default")
      (node (ref "DD1") (pin "5") (pinfunction "5_5") (pintype "bidirectional"))
    )
    (net (code "70") (name "unconnected-(DD2-Pad5)") (class "Default")
      (node (ref "DD2") (pin "5") (pinfunction "5_5") (pintype "bidirectional"))
    )
    (net (code "71") (name "unconnected-(VD1-CMN-Pad3)") (class "Default")
      (node (ref "VD1") (pin "3") (pinfunction "CMN_3") (pintype "passive"))
    )
    (net (code "72") (name "unconnected-(VD2-CMN-Pad3)") (class "Default")
      (node (ref "VD2") (pin "3") (pinfunction "CMN_3") (pintype "passive"))
    )
    (net (code "73") (name "unconnected-(VD3-CMN-Pad3)") (class "Default")
      (node (ref "VD3") (pin "3") (pinfunction "CMN_3") (pintype "passive"))
    )
    (net (code "74") (name "unconnected-(VD4-CMN-Pad3)") (class "Default")
      (node (ref "VD4") (pin "3") (pinfunction "CMN_3") (pintype "passive"))
    )
  )
)
